# H0AR3_Frontend.net
KiCad netlist of a schematic drawn in Altium Designer
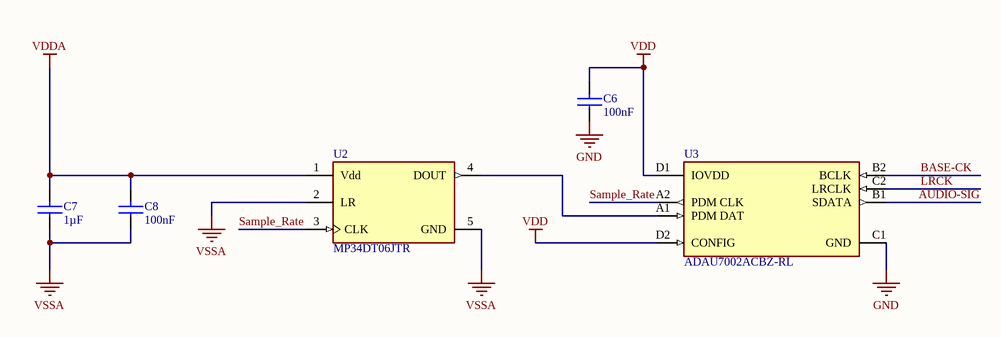
[diagram p0: H0AR3_Frontend.SchDoc]

(export (version "E")
  (design (tool "Eeschema 10.0.6"))
  (components
    (comp (ref "C6")
      (value "100nF")
      (footprint "C0603")
      (fields
        (field (name "MANUFACTURER") "Samsung Electro-Mechanics")
        (field (name "MANUFACTURER PART NUMBER") "CL10B104KA8NNNC")
        (field (name "TOLERANCE") "10%")
      )
      (libsource (lib "Hexabitz Altium Library") (part "generic Capacitor"))
    )
    (comp (ref "C7")
      (value "1µF")
      (footprint "C0805")
      (description "Ceramic Capacitor, Ceramic, 16V, 10% +Tol, 10% -Tol, X7R, 15% TC, 1uF, Surface Mount, 0805")
      (fields
        (field (name "MANUFACTURER") "Yageo Group")
        (field (name "MANUFACTURER PART NUMBER") "CC0805KKX7R7BB105")
      )
      (libsource (lib "Hexabitz Altium Library") (part "generic Capacitor"))
    )
    (comp (ref "C8")
      (value "100nF")
      (footprint "C0603")
      (fields
        (field (name "MANUFACTURER") "Samsung Electro-Mechanics")
        (field (name "MANUFACTURER PART NUMBER") "CL10B104KA8NNNC")
        (field (name "TOLERANCE") "10%")
      )
      (libsource (lib "Hexabitz Altium Library") (part "generic Capacitor"))
    )
    (comp (ref "U2")
      (value "MP34DT06JTR")
      (footprint "FP-HCLGA4-DM00231908-MFG")
      (description "MEMS AUDIO SENSOR OMNIDIRECTIONA")
      (fields
        (field (name "MANUFACTURER") "STMicroelectronics")
        (field (name "OCTOPART") "https://octopart.com/mp34dt06jtr-stmicroelectronics-94413825")
      )
      (libsource (lib "Altium Content Vault") (part "1f09fff9aa5ba159ad793fb03c9bd88"))
    )
    (comp (ref "U3")
      (value "ADAU7002ACBZ-RL")
      (footprint "FP-CB-8-6-IPC_B")
      (description "IC SAMPLE RATE CONVERTER 8WLCSP")
      (libsource (lib "Altium Content Vault") (part "733fa76a9435a4818337fa63b2bd65c"))
    )
  )
  (nets
    (net (code "1") (name "/AUDIO-SIG") (class "Default")
      (node (ref "U3") (pin "B1") (pinfunction "SDATA_B1") (pintype "output"))
    )
    (net (code "2") (name "/BASE-CK") (class "Default")
      (node (ref "U3") (pin "B2") (pinfunction "BCLK_B2") (pintype "input"))
    )
    (net (code "3") (name "/LRCK") (class "Default")
      (node (ref "U3") (pin "C2") (pinfunction "LRCLK_C2") (pintype "input"))
    )
    (net (code "4") (name "/Sample_Rate") (class "Default")
      (node (ref "U2") (pin "3") (pinfunction "CLK_3") (pintype "input"))
      (node (ref "U3") (pin "A2") (pinfunction "PDM_CLK_A2") (pintype "output"))
    )
    (net (code "5") (name "GND") (class "Default")
      (node (ref "C6") (pin "1") (pinfunction "1_1") (pintype "passive"))
      (node (ref "U3") (pin "C1") (pinfunction "GND_C1") (pintype "power_in"))
    )
    (net (code "6") (name "Net-(U2-DOUT)") (class "Default")
      (node (ref "U2") (pin "4") (pinfunction "DOUT_4") (pintype "output"))
      (node (ref "U3") (pin "A1") (pinfunction "PDM_DAT_A1") (pintype "input"))
    )
    (net (code "7") (name "VDD") (class "Default")
      (node (ref "C6") (pin "2") (pinfunction "2_2") (pintype "passive"))
      (node (ref "U3") (pin "D1") (pinfunction "IOVDD_D1") (pintype "power_in"))
      (node (ref "U3") (pin "D2") (pinfunction "CONFIG_D2") (pintype "input"))
    )
    (net (code "8") (name "VDDA") (class "Default")
      (node (ref "C7") (pin "2") (pinfunction "2_2") (pintype "passive"))
      (node (ref "C8") (pin "2") (pinfunction "2_2") (pintype "passive"))
      (node (ref "U2") (pin "1") (pinfunction "Vdd_1") (pintype "power_in"))
    )
    (net (code "9") (name "VSSA") (class "Default")
      (node (ref "C7") (pin "1") (pinfunction "1_1") (pintype "passive"))
      (node (ref "C8") (pin "1") (pinfunction "1_1") (pintype "passive"))
      (node (ref "U2") (pin "2") (pinfunction "LR_2") (pintype "passive"))
      (node (ref "U2") (pin "5") (pinfunction "GND_5") (pintype "power_in"))
    )
  )
)
